# esp8266_programmer.net
KiCad netlist of a schematic drawn in EAGLE
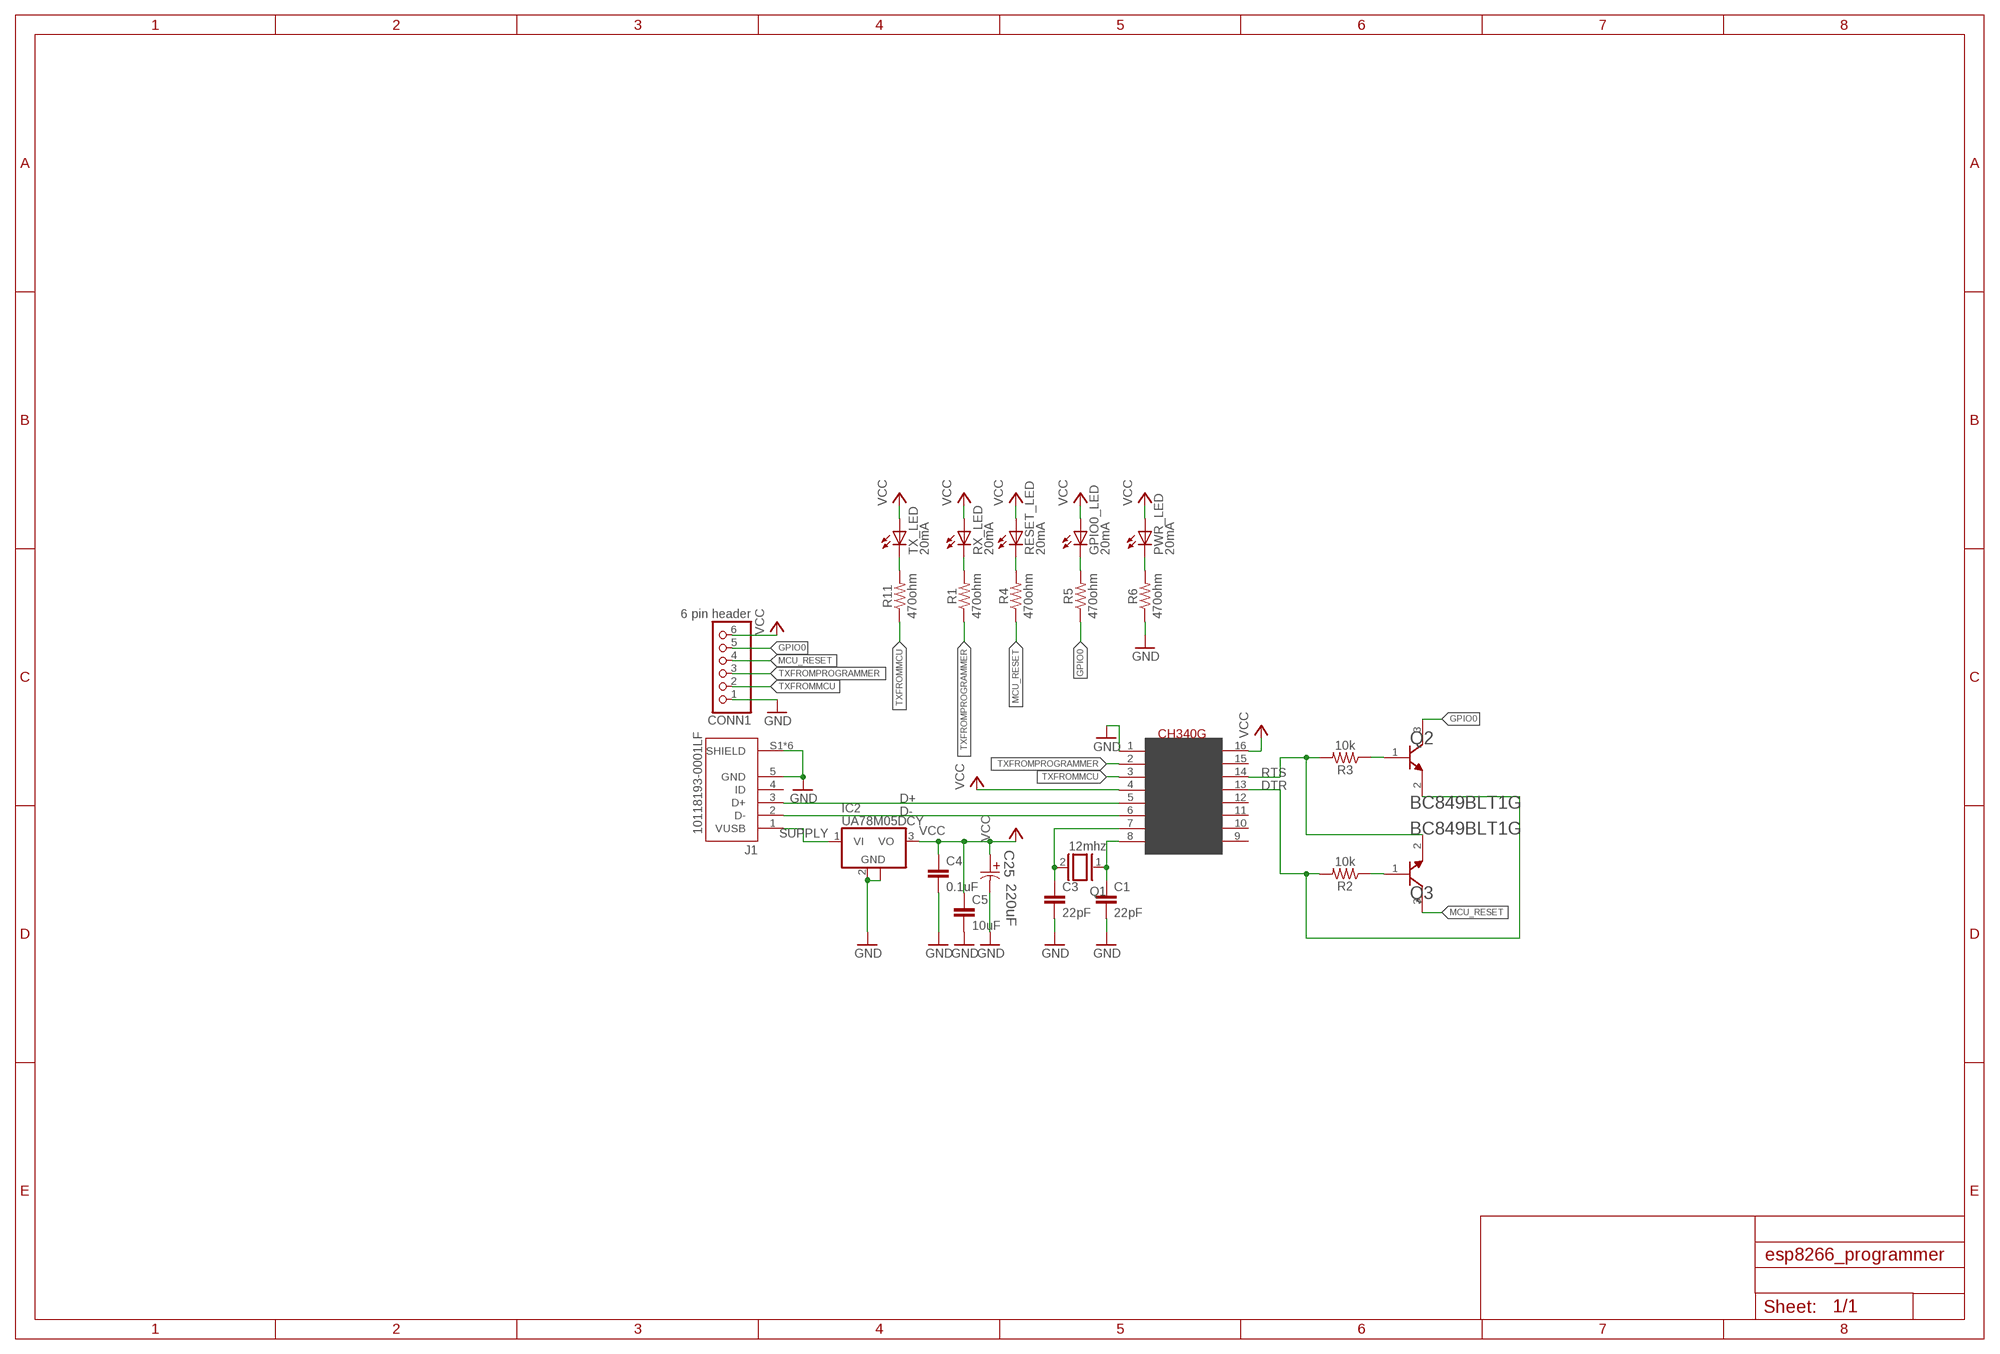
[diagram p0: schematic, sheet 1]

(export (version "E")
  (design (tool "Eeschema 10.0.6"))
  (components
    (comp (ref "C1")
      (value "22pF")
      (footprint "eagle-import:C0603")
      (libsource (lib "eagle-import") (part "C-EUC0603"))
    )
    (comp (ref "C3")
      (value "22pF")
      (footprint "eagle-import:C0603")
      (libsource (lib "eagle-import") (part "C-EUC0603"))
    )
    (comp (ref "C4")
      (value "0.1uF")
      (footprint "eagle-import:C0603")
      (libsource (lib "eagle-import") (part "C-EUC0603"))
    )
    (comp (ref "C5")
      (value "10uF")
      (footprint "eagle-import:C0603")
      (libsource (lib "eagle-import") (part "C-EUC0603"))
    )
    (comp (ref "C25")
      (value "220uF")
      (footprint "eagle-import:CAPAE830X1050N")
      (fields (field (name "MPN") "EEE-FK1C471P") (field (name "TOLERANCE") "±20 %"))
      (libsource (lib "eagle-import") (part "EEE--CASE-FFK1C471P"))
    )
    (comp (ref "CONN1")
      (value "6 pin header")
      (footprint "eagle-import:1X06")
      (libsource (lib "eagle-import") (part "PINHD-1X6"))
    )
    (comp (ref "GPIO0_LED")
      (value "20mA")
      (footprint "eagle-import:CHIP-LED0603")
      (libsource (lib "eagle-import") (part "LEDCHIP-LED0603"))
    )
    (comp (ref "IC2")
      (value "UA78M05DCY")
      (footprint "eagle-import:SOT223")
      (libsource (lib "eagle-import") (part "UA78MDCY05"))
    )
    (comp (ref "J1")
      (value "10118193-0001LF")
      (footprint "eagle-import:FCI_10118193-0001LF")
      (fields (field (name "MF") "Amphenol FCI"))
      (libsource (lib "eagle-import") (part "10118193-0001LF"))
    )
    (comp (ref "PWR_LED")
      (value "20mA")
      (footprint "eagle-import:CHIP-LED0603")
      (libsource (lib "eagle-import") (part "LEDCHIP-LED0603"))
    )
    (comp (ref "Q1")
      (value "12mhz")
      (footprint "eagle-import:QS")
      (libsource (lib "eagle-import") (part "XTAL/S"))
    )
    (comp (ref "Q2")
      (value "ON_SEMICONDUCTOR_BC849BLT1GON_SEMICONDUCTOR_BC849BLT1G_0_0")
      (footprint "eagle-import:ON_SEMICONDUCTOR_BC849BLT1G_0")
      (fields (field (name "MF") "On Semiconductor") (field (name "MPN") "BC849BLT1G"))
      (libsource (lib "eagle-import") (part "ON_SEMICONDUCTOR_BC849BLT1GON_SEMICONDUCTOR_BC849BLT1G_0_0"))
    )
    (comp (ref "Q3")
      (value "ON_SEMICONDUCTOR_BC849BLT1GON_SEMICONDUCTOR_BC849BLT1G_0_0")
      (footprint "eagle-import:ON_SEMICONDUCTOR_BC849BLT1G_0")
      (fields (field (name "MF") "On Semiconductor") (field (name "MPN") "BC849BLT1G"))
      (libsource (lib "eagle-import") (part "ON_SEMICONDUCTOR_BC849BLT1GON_SEMICONDUCTOR_BC849BLT1G_0_0"))
    )
    (comp (ref "R1")
      (value "470ohm")
      (footprint "eagle-import:0603")
      (libsource (lib "eagle-import") (part "10KOHM-0603-1/10W-1%"))
    )
    (comp (ref "R2")
      (value "10k")
      (footprint "eagle-import:0603")
      (libsource (lib "eagle-import") (part "10KOHM-0603-1/10W-1%"))
    )
    (comp (ref "R3")
      (value "10k")
      (footprint "eagle-import:0603")
      (libsource (lib "eagle-import") (part "10KOHM-0603-1/10W-1%"))
    )
    (comp (ref "R4")
      (value "470ohm")
      (footprint "eagle-import:0603")
      (libsource (lib "eagle-import") (part "10KOHM-0603-1/10W-1%"))
    )
    (comp (ref "R5")
      (value "470ohm")
      (footprint "eagle-import:0603")
      (libsource (lib "eagle-import") (part "10KOHM-0603-1/10W-1%"))
    )
    (comp (ref "R6")
      (value "470ohm")
      (footprint "eagle-import:0603")
      (libsource (lib "eagle-import") (part "10KOHM-0603-1/10W-1%"))
    )
    (comp (ref "R11")
      (value "470ohm")
      (footprint "eagle-import:0603")
      (libsource (lib "eagle-import") (part "10KOHM-0603-1/10W-1%"))
    )
    (comp (ref "RESET_LED")
      (value "20mA")
      (footprint "eagle-import:CHIP-LED0603")
      (libsource (lib "eagle-import") (part "LEDCHIP-LED0603"))
    )
    (comp (ref "RX_LED")
      (value "20mA")
      (footprint "eagle-import:CHIP-LED0603")
      (libsource (lib "eagle-import") (part "LEDCHIP-LED0603"))
    )
    (comp (ref "TX_LED")
      (value "20mA")
      (footprint "eagle-import:CHIP-LED0603")
      (libsource (lib "eagle-import") (part "LEDCHIP-LED0603"))
    )
    (comp (ref "U$1")
      (value "CH340G")
      (footprint "eagle-import:SOIC16")
      (libsource (lib "eagle-import") (part "CH340G"))
    )
  )
  (nets
    (net (code "1") (name "/D+") (class "Default")
      (node (ref "J1") (pin "3") (pinfunction "D+_3") (pintype "passive"))
      (node (ref "U$1") (pin "5") (pinfunction "D+_5") (pintype "bidirectional"))
    )
    (net (code "2") (name "/D-") (class "Default")
      (node (ref "J1") (pin "2") (pinfunction "D-_2") (pintype "passive"))
      (node (ref "U$1") (pin "6") (pinfunction "D-_6") (pintype "bidirectional"))
    )
    (net (code "3") (name "/DTR") (class "Default")
      (node (ref "Q2") (pin "2") (pinfunction "E_2") (pintype "passive"))
      (node (ref "R2") (pin "2") (pinfunction "2_2") (pintype "passive"))
      (node (ref "U$1") (pin "13") (pinfunction "DTR_13") (pintype "bidirectional"))
    )
    (net (code "4") (name "/RTS") (class "Default")
      (node (ref "Q3") (pin "2") (pinfunction "E_2") (pintype "passive"))
      (node (ref "R3") (pin "2") (pinfunction "2_2") (pintype "passive"))
      (node (ref "U$1") (pin "14") (pinfunction "RTS_14") (pintype "bidirectional"))
    )
    (net (code "5") (name "/SUPPLY") (class "Default")
      (node (ref "IC2") (pin "1") (pinfunction "VI_1") (pintype "input"))
      (node (ref "J1") (pin "1") (pinfunction "VUSB_1") (pintype "passive"))
    )
    (net (code "6") (name "GND") (class "Default")
      (node (ref "C1") (pin "2") (pinfunction "2_2") (pintype "passive"))
      (node (ref "C25") (pin "2") (pinfunction "2_2") (pintype "passive"))
      (node (ref "C3") (pin "2") (pinfunction "2_2") (pintype "passive"))
      (node (ref "C4") (pin "2") (pinfunction "2_2") (pintype "passive"))
      (node (ref "C5") (pin "2") (pinfunction "2_2") (pintype "passive"))
      (node (ref "CONN1") (pin "1") (pinfunction "1_1") (pintype "passive"))
      (node (ref "IC2") (pin "2") (pinfunction "GND_2") (pintype "passive"))
      (node (ref "IC2") (pin "4") (pinfunction "GND_4") (pintype "passive"))
      (node (ref "J1") (pin "5") (pinfunction "GND_5") (pintype "passive"))
      (node (ref "J1") (pin "S1") (pinfunction "SHIELD_S1") (pintype "passive"))
      (node (ref "J1") (pin "S2") (pinfunction "SHIELD_S2") (pintype "passive"))
      (node (ref "J1") (pin "S3") (pinfunction "SHIELD_S3") (pintype "passive"))
      (node (ref "J1") (pin "S4") (pinfunction "SHIELD_S4") (pintype "passive"))
      (node (ref "J1") (pin "S5") (pinfunction "SHIELD_S5") (pintype "passive"))
      (node (ref "J1") (pin "S6") (pinfunction "SHIELD_S6") (pintype "passive"))
      (node (ref "R6") (pin "1") (pinfunction "1_1") (pintype "passive"))
      (node (ref "U$1") (pin "1") (pinfunction "GND_1") (pintype "bidirectional"))
    )
    (net (code "7") (name "GPIO0") (class "Default")
      (node (ref "CONN1") (pin "5") (pinfunction "5_5") (pintype "passive"))
      (node (ref "Q2") (pin "3") (pinfunction "C_3") (pintype "passive"))
      (node (ref "R5") (pin "1") (pinfunction "1_1") (pintype "passive"))
    )
    (net (code "8") (name "MCU_RESET") (class "Default")
      (node (ref "CONN1") (pin "4") (pinfunction "4_4") (pintype "passive"))
      (node (ref "Q3") (pin "3") (pinfunction "C_3") (pintype "passive"))
      (node (ref "R4") (pin "1") (pinfunction "1_1") (pintype "passive"))
    )
    (net (code "9") (name "Net-(GPIO0_LED-PadC)") (class "Default")
      (node (ref "GPIO0_LED") (pin "C") (pinfunction "C_C") (pintype "passive"))
      (node (ref "R5") (pin "2") (pinfunction "2_2") (pintype "passive"))
    )
    (net (code "10") (name "Net-(PWR_LED-PadC)") (class "Default")
      (node (ref "PWR_LED") (pin "C") (pinfunction "C_C") (pintype "passive"))
      (node (ref "R6") (pin "2") (pinfunction "2_2") (pintype "passive"))
    )
    (net (code "11") (name "Net-(Q2-B)") (class "Default")
      (node (ref "Q2") (pin "1") (pinfunction "B_1") (pintype "passive"))
      (node (ref "R3") (pin "1") (pinfunction "1_1") (pintype "passive"))
    )
    (net (code "12") (name "Net-(Q3-B)") (class "Default")
      (node (ref "Q3") (pin "1") (pinfunction "B_1") (pintype "passive"))
      (node (ref "R2") (pin "1") (pinfunction "1_1") (pintype "passive"))
    )
    (net (code "13") (name "Net-(R1-Pad2)") (class "Default")
      (node (ref "R1") (pin "2") (pinfunction "2_2") (pintype "passive"))
      (node (ref "RX_LED") (pin "C") (pinfunction "C_C") (pintype "passive"))
    )
    (net (code "14") (name "Net-(R4-Pad2)") (class "Default")
      (node (ref "R4") (pin "2") (pinfunction "2_2") (pintype "passive"))
      (node (ref "RESET_LED") (pin "C") (pinfunction "C_C") (pintype "passive"))
    )
    (net (code "15") (name "Net-(R11-Pad2)") (class "Default")
      (node (ref "R11") (pin "2") (pinfunction "2_2") (pintype "passive"))
      (node (ref "TX_LED") (pin "C") (pinfunction "C_C") (pintype "passive"))
    )
    (net (code "16") (name "Net-(U$1-XI)") (class "Default")
      (node (ref "C3") (pin "1") (pinfunction "1_1") (pintype "passive"))
      (node (ref "Q1") (pin "2") (pinfunction "2_2") (pintype "passive"))
      (node (ref "U$1") (pin "7") (pinfunction "XI_7") (pintype "bidirectional"))
    )
    (net (code "17") (name "Net-(U$1-XO)") (class "Default")
      (node (ref "C1") (pin "1") (pinfunction "1_1") (pintype "passive"))
      (node (ref "Q1") (pin "1") (pinfunction "1_1") (pintype "passive"))
      (node (ref "U$1") (pin "8") (pinfunction "XO_8") (pintype "bidirectional"))
    )
    (net (code "18") (name "TXFROMMCU") (class "Default")
      (node (ref "CONN1") (pin "2") (pinfunction "2_2") (pintype "passive"))
      (node (ref "R11") (pin "1") (pinfunction "1_1") (pintype "passive"))
      (node (ref "U$1") (pin "3") (pinfunction "RX_3") (pintype "bidirectional"))
    )
    (net (code "19") (name "TXFROMPROGRAMMER") (class "Default")
      (node (ref "CONN1") (pin "3") (pinfunction "3_3") (pintype "passive"))
      (node (ref "R1") (pin "1") (pinfunction "1_1") (pintype "passive"))
      (node (ref "U$1") (pin "2") (pinfunction "TX_2") (pintype "bidirectional"))
    )
    (net (code "20") (name "VCC") (class "Default")
      (node (ref "C25") (pin "1") (pinfunction "1_1") (pintype "passive"))
      (node (ref "C4") (pin "1") (pinfunction "1_1") (pintype "passive"))
      (node (ref "C5") (pin "1") (pinfunction "1_1") (pintype "passive"))
      (node (ref "CONN1") (pin "6") (pinfunction "6_6") (pintype "passive"))
      (node (ref "GPIO0_LED") (pin "A") (pinfunction "A_A") (pintype "passive"))
      (node (ref "IC2") (pin "3") (pinfunction "VO_3") (pintype "passive"))
      (node (ref "PWR_LED") (pin "A") (pinfunction "A_A") (pintype "passive"))
      (node (ref "RESET_LED") (pin "A") (pinfunction "A_A") (pintype "passive"))
      (node (ref "RX_LED") (pin "A") (pinfunction "A_A") (pintype "passive"))
      (node (ref "TX_LED") (pin "A") (pinfunction "A_A") (pintype "passive"))
      (node (ref "U$1") (pin "16") (pinfunction "VCC_16") (pintype "bidirectional"))
      (node (ref "U$1") (pin "4") (pinfunction "V3_4") (pintype "bidirectional"))
    )
    (net (code "21") (name "unconnected-(J1-ID-Pad4)") (class "Default")
      (node (ref "J1") (pin "4") (pinfunction "ID_4") (pintype "passive"))
    )
    (net (code "22") (name "unconnected-(U$1-CTS-Pad9)") (class "Default")
      (node (ref "U$1") (pin "9") (pinfunction "CTS_9") (pintype "bidirectional"))
    )
    (net (code "23") (name "unconnected-(U$1-DCD-Pad12)") (class "Default")
      (node (ref "U$1") (pin "12") (pinfunction "DCD_12") (pintype "bidirectional"))
    )
    (net (code "24") (name "unconnected-(U$1-DSR-Pad10)") (class "Default")
      (node (ref "U$1") (pin "10") (pinfunction "DSR_10") (pintype "bidirectional"))
    )
    (net (code "25") (name "unconnected-(U$1-RI-Pad11)") (class "Default")
      (node (ref "U$1") (pin "11") (pinfunction "RI_11") (pintype "bidirectional"))
    )
    (net (code "26") (name "unconnected-(U$1-RS232-Pad15)") (class "Default")
      (node (ref "U$1") (pin "15") (pinfunction "RS232_15") (pintype "bidirectional"))
    )
  )
)
